# balanceladder_2026-06-09.net
KiCad netlist of a schematic drawn in EasyEDA Pro
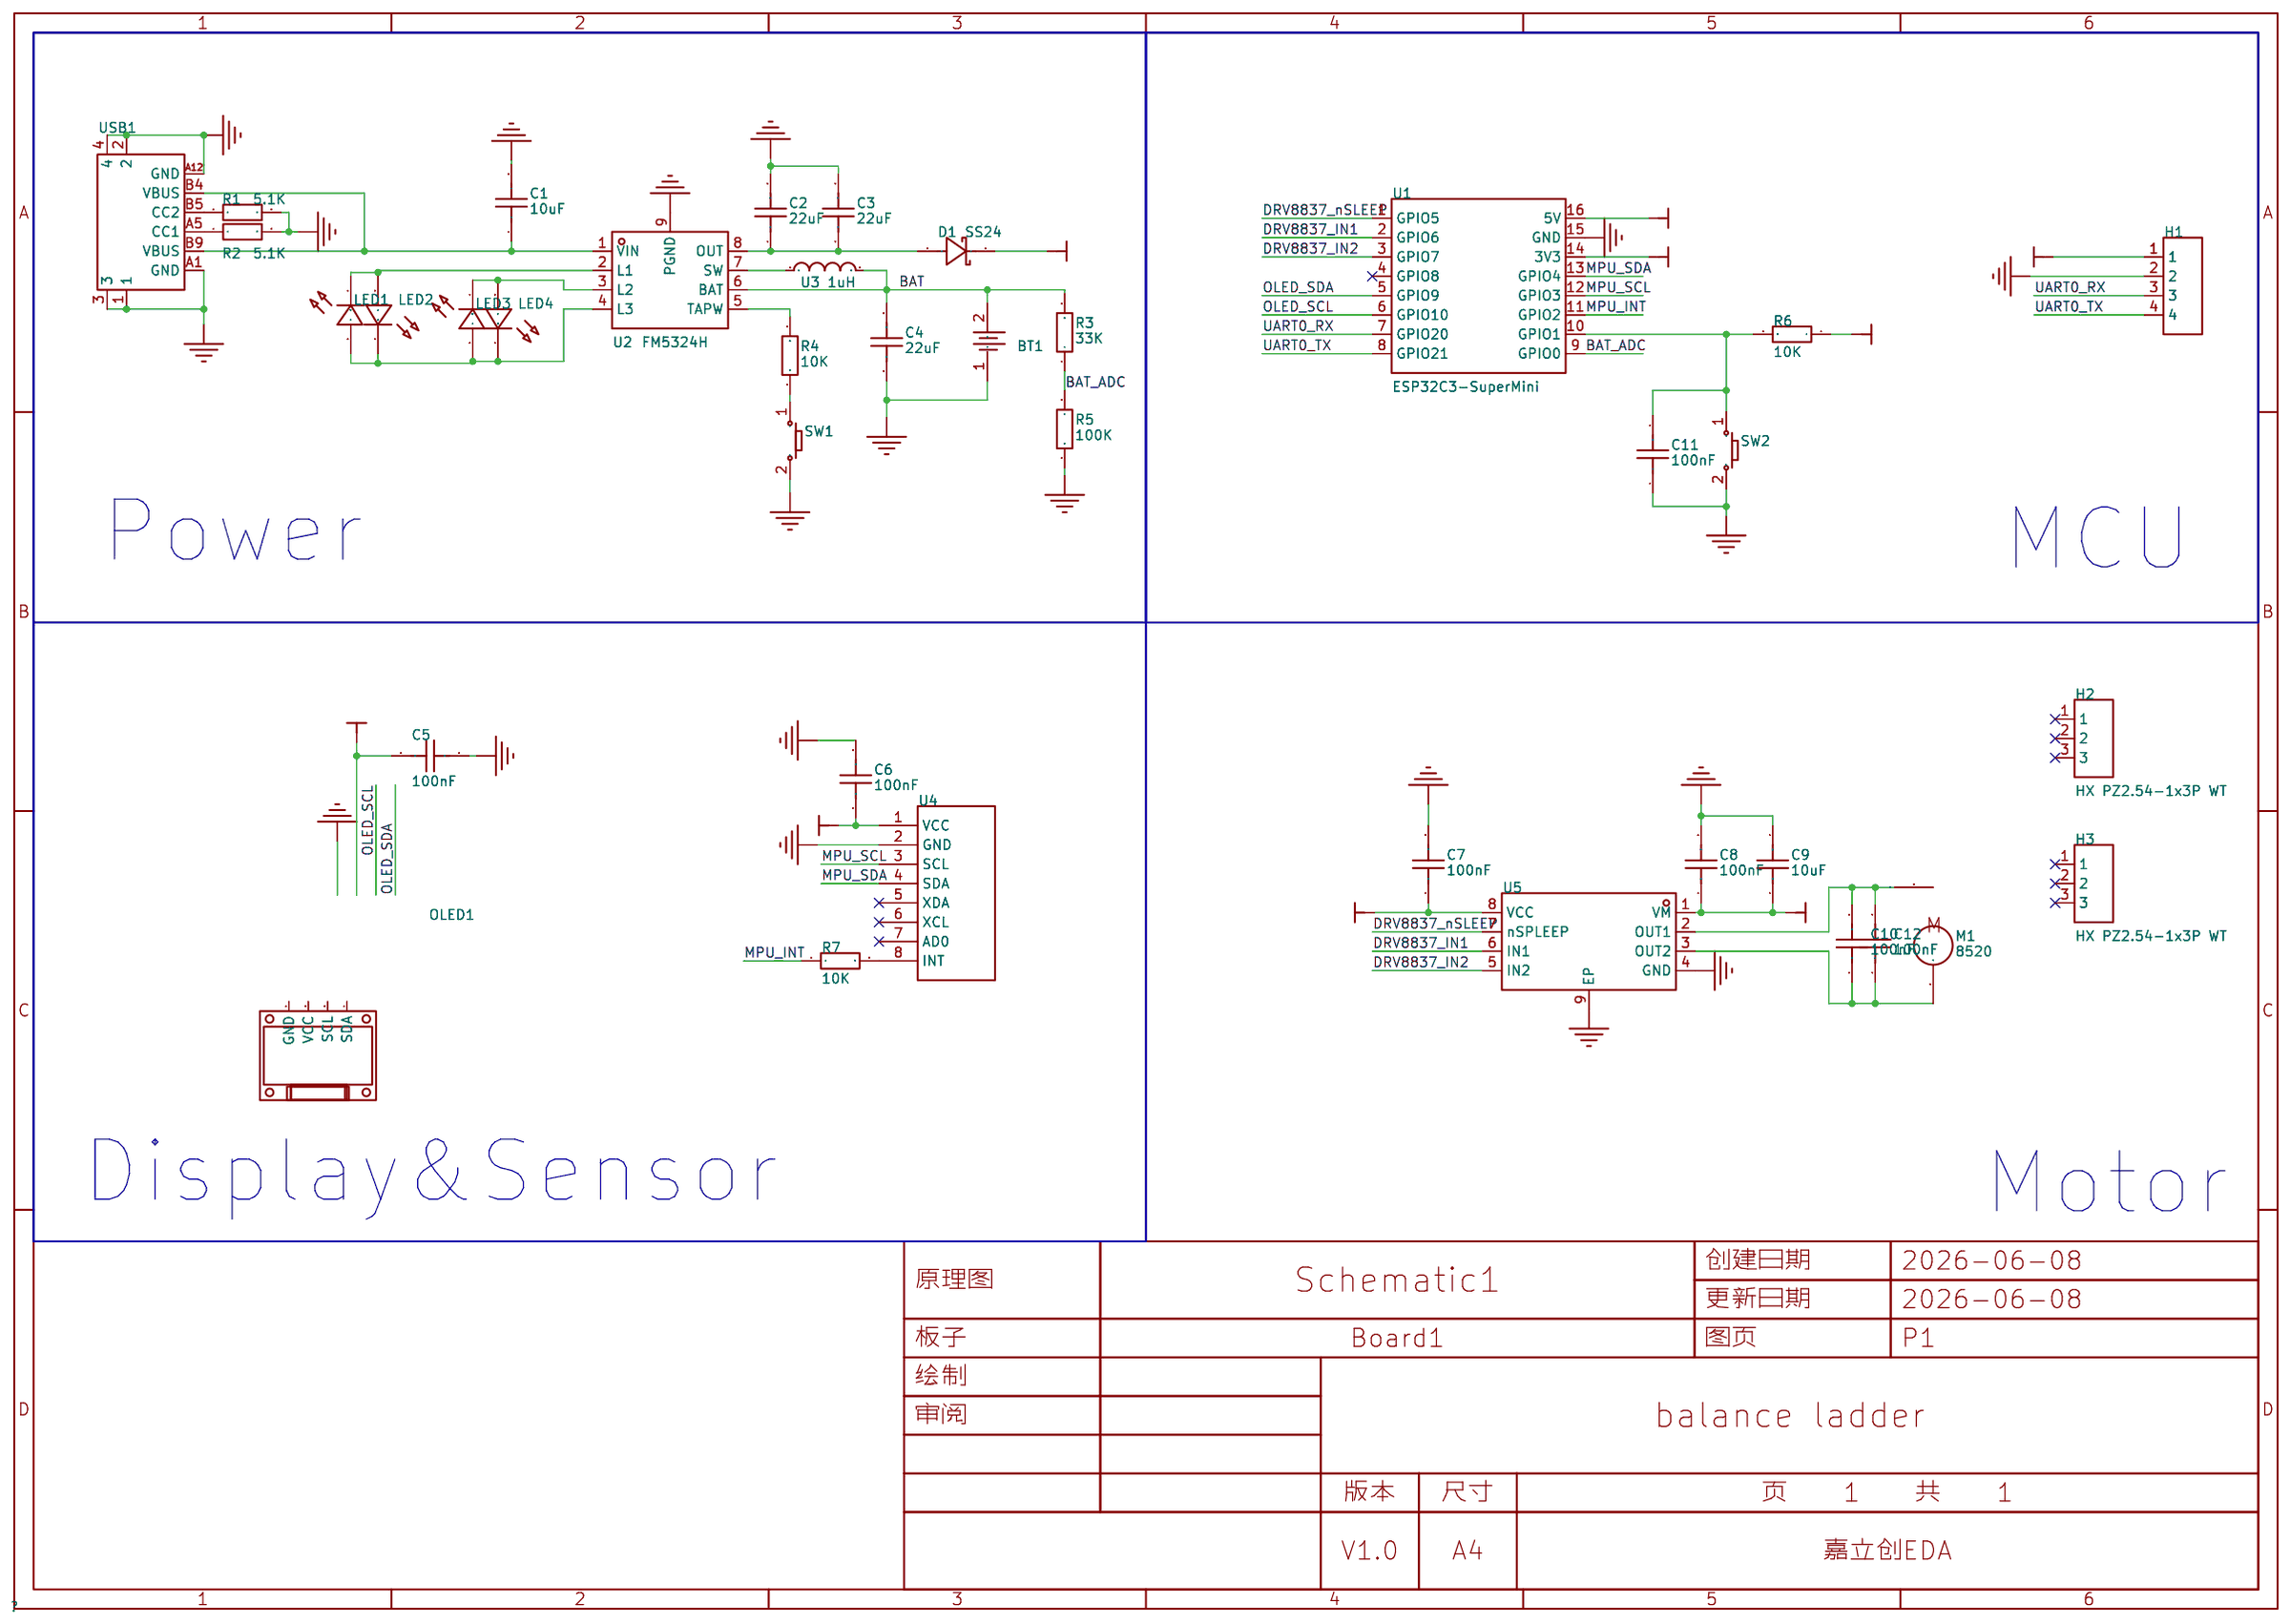
[diagram p0: schematic sheet]

(export (version "E")
  (design (tool "Eeschema 10.0.6"))
  (components
    (comp (ref "BT1")
      (value "BH-18650-B1BA002")
      (footprint "easyedapro:BATTERY-SMD_18650-1S-L77.1-W20.7-1")
      (fields (field (name "Manufacturer") "MYOUNG(美阳)"))
      (libsource (lib "easyedapro") (part "BH-18650-B1BA002"))
    )
    (comp (ref "C1")
      (value "10uF")
      (footprint "easyedapro:C0603")
      (libsource (lib "easyedapro") (part "Capacitance"))
    )
    (comp (ref "C2")
      (value "22uF")
      (footprint "easyedapro:C0603")
      (libsource (lib "easyedapro") (part "Capacitance"))
    )
    (comp (ref "C3")
      (value "22uF")
      (footprint "easyedapro:C0603")
      (libsource (lib "easyedapro") (part "Capacitance"))
    )
    (comp (ref "C4")
      (value "22uF")
      (footprint "easyedapro:C0603")
      (libsource (lib "easyedapro") (part "Capacitance"))
    )
    (comp (ref "C5")
      (value "100nF")
      (footprint "easyedapro:C0402")
      (fields
        (field (name "Manufacturer Part") "CL05B104KO5NNNC")
        (field (name "Manufacturer") "SAMSUNG(三星)")
      )
      (libsource (lib "easyedapro") (part "CL05B104KO5NNNC"))
    )
    (comp (ref "C6")
      (value "100nF")
      (footprint "easyedapro:C0402")
      (fields
        (field (name "Manufacturer Part") "CL05B104KO5NNNC")
        (field (name "Manufacturer") "SAMSUNG(三星)")
      )
      (libsource (lib "easyedapro") (part "CL05B104KO5NNNC"))
    )
    (comp (ref "C7")
      (value "100nF")
      (footprint "easyedapro:C0402")
      (fields
        (field (name "Manufacturer Part") "CL05B104KO5NNNC")
        (field (name "Manufacturer") "SAMSUNG(三星)")
      )
      (libsource (lib "easyedapro") (part "CL05B104KO5NNNC"))
    )
    (comp (ref "C8")
      (value "100nF")
      (footprint "easyedapro:C0402")
      (fields
        (field (name "Manufacturer Part") "CL05B104KO5NNNC")
        (field (name "Manufacturer") "SAMSUNG(三星)")
      )
      (libsource (lib "easyedapro") (part "CL05B104KO5NNNC"))
    )
    (comp (ref "C9")
      (value "10uF")
      (footprint "easyedapro:C0603")
      (libsource (lib "easyedapro") (part "Capacitance"))
    )
    (comp (ref "C10")
      (value "100nF")
      (footprint "easyedapro:C0402")
      (fields
        (field (name "Manufacturer Part") "CL05B104KO5NNNC")
        (field (name "Manufacturer") "SAMSUNG(三星)")
      )
      (libsource (lib "easyedapro") (part "CL05B104KO5NNNC"))
    )
    (comp (ref "C11")
      (value "100nF")
      (footprint "easyedapro:C0402")
      (description "容值:100nF;精度:±10%;额定电压:16V;温度系数:X7R;")
      (fields
        (field (name "Manufacturer Part") "CL05B104KO5NNNC")
        (field (name "Manufacturer") "SAMSUNG(三星)")
      )
      (libsource (lib "easyedapro") (part "CL05B104KO5NNNC"))
    )
    (comp (ref "C12")
      (value "100nF")
      (footprint "easyedapro:C0402")
      (description "容值:100nF;精度:±10%;额定电压:16V;温度系数:X7R;")
      (fields
        (field (name "Manufacturer Part") "CL05B104KO5NNNC")
        (field (name "Manufacturer") "SAMSUNG(三星)")
      )
      (libsource (lib "easyedapro") (part "CL05B104KO5NNNC"))
    )
    (comp (ref "D1")
      (value "SS24")
      (footprint "easyedapro:SMA_L4.3-W2.6-LS5.0-FD")
      (fields (field (name "Manufacturer") "R+O(宏嘉诚)"))
      (libsource (lib "easyedapro") (part "SS24_C7420362"))
    )
    (comp (ref "H1")
      (value "HX PZ2.54-1x4P WT")
      (footprint "easyedapro:CONN-SMD_HX-PZ2.54-1X4P-WT")
      (fields (field (name "Manufacturer") "hanxia(韩下)"))
      (libsource (lib "easyedapro") (part "HX PZ2.54-1X4P WT"))
    )
    (comp (ref "H2")
      (value "HX PZ2.54-1x3P WT")
      (footprint "easyedapro:HDR-SMD_3P-P2.54-H-M_KH-2.54PH-1X3P-L13.5-WT")
      (fields (field (name "Manufacturer") "hanxia(韩下)"))
      (libsource (lib "easyedapro") (part "HX PZ2.54-1X3P WT"))
    )
    (comp (ref "H3")
      (value "HX PZ2.54-1x3P WT")
      (footprint "easyedapro:HDR-SMD_3P-P2.54-H-M_KH-2.54PH-1X3P-L13.5-WT")
      (fields (field (name "Manufacturer") "hanxia(韩下)"))
      (libsource (lib "easyedapro") (part "HX PZ2.54-1X3P WT"))
    )
    (comp (ref "LED1")
      (value "~")
      (footprint "easyedapro:LED_0603")
      (libsource (lib "easyedapro") (part "LED_G"))
    )
    (comp (ref "LED2")
      (value "~")
      (footprint "easyedapro:LED_0603")
      (libsource (lib "easyedapro") (part "LED_G"))
    )
    (comp (ref "LED3")
      (value "~")
      (footprint "easyedapro:LED_0603")
      (libsource (lib "easyedapro") (part "LED_G"))
    )
    (comp (ref "LED4")
      (value "~")
      (footprint "easyedapro:LED_0603")
      (libsource (lib "easyedapro") (part "LED_G"))
    )
    (comp (ref "M1") (value "8520") (libsource (lib "easyedapro") (part "Motor")))
    (comp (ref "OLED1")
      (value "~")
      (footprint "easyedapro:0.96OLED_4P")
      (libsource (lib "easyedapro") (part "0.96OLED模块_4P"))
    )
    (comp (ref "R1") (value "5.1K") (footprint "easyedapro:R0603") (libsource (lib "easyedapro") (part "电阻")))
    (comp (ref "R2") (value "5.1K") (footprint "easyedapro:R0603") (libsource (lib "easyedapro") (part "电阻")))
    (comp (ref "R3") (value "33K") (footprint "easyedapro:R0603") (libsource (lib "easyedapro") (part "电阻")))
    (comp (ref "R4") (value "10K") (footprint "easyedapro:R0603") (libsource (lib "easyedapro") (part "电阻")))
    (comp (ref "R5") (value "100K") (footprint "easyedapro:R0603") (libsource (lib "easyedapro") (part "电阻")))
    (comp (ref "R6") (value "10K") (footprint "easyedapro:R0603") (libsource (lib "easyedapro") (part "电阻")))
    (comp (ref "R7") (value "10K") (footprint "easyedapro:R0402") (libsource (lib "easyedapro") (part "电阻")))
    (comp (ref "SW1")
      (value "~")
      (footprint "easyedapro:Key_SMD_3x4x2")
      (libsource (lib "easyedapro") (part "轻触按键x2"))
    )
    (comp (ref "SW2")
      (value "~")
      (footprint "easyedapro:Key_SMD_3x4x2")
      (libsource (lib "easyedapro") (part "轻触按键x2"))
    )
    (comp (ref "U1")
      (value "ESP32C3-SuperMini")
      (footprint "easyedapro:COMM-SMD_16P-L22.5-W18.0-P2.54-TL")
      (libsource (lib "easyedapro") (part "ESP32C3-SUPERMINI"))
    )
    (comp (ref "U2")
      (value "FM5324H")
      (footprint "easyedapro:ESOP-8_L4.9-W3.9-P1.27-LS6.0-BL-EP3.1")
      (fields (field (name "Manufacturer") "FM(富满)"))
      (libsource (lib "easyedapro") (part "FM5324H"))
    )
    (comp (ref "U3")
      (value "1uH")
      (footprint "easyedapro:IND-SMD_L2.5-W2.0-VLS252012CX-150M")
      (description "电感值:1uH;精度:±20%;额定电流:4A;饱和电流(Isat):5.6A;类型:-;")
      (fields
        (field (name "Manufacturer Part") "FTC252012S1R0MBCA")
        (field (name "Manufacturer") "cjiang(长江微电)")
      )
      (libsource (lib "easyedapro") (part "FTC252012S1R0MBCA"))
    )
    (comp (ref "U4") (value "~") (footprint "easyedapro:GY521") (libsource (lib "easyedapro") (part "GY521")))
    (comp (ref "U5")
      (value "DRV8837DSGR")
      (footprint "easyedapro:WSON-8_L2.0-W2.0-P0.50-TL-EP")
      (fields (field (name "Manufacturer") "TI(德州仪器)"))
      (libsource (lib "easyedapro") (part "DRV8837DSGR"))
    )
    (comp (ref "USB1")
      (value "HYCW574-USBC06-650B")
      (footprint "easyedapro:USB-C-SMD_HYCW574-USBC06-650B")
      (fields (field (name "Manufacturer") "HOAUC(华宇创)"))
      (libsource (lib "easyedapro") (part "HYCW574-USBC06-650B"))
    )
  )
  (nets
    (net (code "1") (name "+5V") (class "Default")
      (node (ref "C8") (pin "1") (pinfunction "1_1") (pintype "unspecified"))
      (node (ref "C9") (pin "1") (pinfunction "1_1") (pintype "input"))
      (node (ref "D1") (pin "2") (pinfunction "K_2") (pintype "unspecified"))
      (node (ref "U1") (pin "16") (pinfunction "5V_16") (pintype "unspecified"))
      (node (ref "U5") (pin "1") (pinfunction "VM_1") (pintype "unspecified"))
    )
    (net (code "2") (name "/BAT") (class "Default")
      (node (ref "BT1") (pin "2") (pinfunction "2_2") (pintype "input"))
      (node (ref "C4") (pin "2") (pinfunction "2_2") (pintype "input"))
      (node (ref "R3") (pin "2") (pinfunction "2_2") (pintype "input"))
      (node (ref "U2") (pin "6") (pinfunction "BAT_6") (pintype "unspecified"))
      (node (ref "U3") (pin "2") (pinfunction "2_2") (pintype "unspecified"))
    )
    (net (code "3") (name "/BAT_ADC") (class "Default")
      (node (ref "R3") (pin "1") (pinfunction "1_1") (pintype "input"))
      (node (ref "R5") (pin "2") (pinfunction "2_2") (pintype "input"))
      (node (ref "U1") (pin "9") (pinfunction "GPIO0_9") (pintype "unspecified"))
    )
    (net (code "4") (name "/DRV8837_IN1") (class "Default")
      (node (ref "U1") (pin "2") (pinfunction "GPIO6_2") (pintype "unspecified"))
      (node (ref "U5") (pin "6") (pinfunction "IN1_6") (pintype "unspecified"))
    )
    (net (code "5") (name "/DRV8837_IN2") (class "Default")
      (node (ref "U1") (pin "3") (pinfunction "GPIO7_3") (pintype "unspecified"))
      (node (ref "U5") (pin "5") (pinfunction "IN2_5") (pintype "unspecified"))
    )
    (net (code "6") (name "/DRV8837_nSLEEP") (class "Default")
      (node (ref "U1") (pin "1") (pinfunction "GPIO5_1") (pintype "unspecified"))
      (node (ref "U5") (pin "7") (pinfunction "nSPLEEP_7") (pintype "unspecified"))
    )
    (net (code "7") (name "/MPU_INT") (class "Default")
      (node (ref "R7") (pin "1") (pinfunction "1_1") (pintype "input"))
      (node (ref "U1") (pin "11") (pinfunction "GPIO2_11") (pintype "unspecified"))
    )
    (net (code "8") (name "/MPU_SCL") (class "Default")
      (node (ref "U1") (pin "12") (pinfunction "GPIO3_12") (pintype "unspecified"))
      (node (ref "U4") (pin "3") (pinfunction "SCL_3") (pintype "input"))
    )
    (net (code "9") (name "/MPU_SDA") (class "Default")
      (node (ref "U1") (pin "13") (pinfunction "GPIO4_13") (pintype "unspecified"))
      (node (ref "U4") (pin "4") (pinfunction "SDA_4") (pintype "input"))
    )
    (net (code "10") (name "/OLED_SCL") (class "Default")
      (node (ref "U1") (pin "6") (pinfunction "GPIO10_6") (pintype "unspecified"))
    )
    (net (code "11") (name "/OLED_SDA") (class "Default")
      (node (ref "U1") (pin "5") (pinfunction "GPIO9_5") (pintype "unspecified"))
    )
    (net (code "12") (name "/UART0_RX") (class "Default")
      (node (ref "H1") (pin "3") (pinfunction "3_3") (pintype "unspecified"))
      (node (ref "U1") (pin "7") (pinfunction "GPIO20_7") (pintype "unspecified"))
    )
    (net (code "13") (name "/UART0_TX") (class "Default")
      (node (ref "H1") (pin "4") (pinfunction "4_4") (pintype "unspecified"))
      (node (ref "U1") (pin "8") (pinfunction "GPIO21_8") (pintype "unspecified"))
    )
    (net (code "14") (name "GND") (class "Default")
      (node (ref "BT1") (pin "1") (pinfunction "1_1") (pintype "input"))
      (node (ref "C1") (pin "2") (pinfunction "2_2") (pintype "input"))
      (node (ref "C11") (pin "1") (pinfunction "1_1") (pintype "unspecified"))
      (node (ref "C2") (pin "2") (pinfunction "2_2") (pintype "input"))
      (node (ref "C3") (pin "2") (pinfunction "2_2") (pintype "input"))
      (node (ref "C4") (pin "1") (pinfunction "1_1") (pintype "input"))
      (node (ref "C5") (pin "1") (pinfunction "1_1") (pintype "unspecified"))
      (node (ref "C6") (pin "2") (pinfunction "2_2") (pintype "unspecified"))
      (node (ref "C7") (pin "2") (pinfunction "2_2") (pintype "unspecified"))
      (node (ref "C8") (pin "2") (pinfunction "2_2") (pintype "unspecified"))
      (node (ref "C9") (pin "2") (pinfunction "2_2") (pintype "input"))
      (node (ref "H1") (pin "2") (pinfunction "2_2") (pintype "unspecified"))
      (node (ref "R1") (pin "2") (pinfunction "2_2") (pintype "input"))
      (node (ref "R2") (pin "2") (pinfunction "2_2") (pintype "input"))
      (node (ref "R5") (pin "1") (pinfunction "1_1") (pintype "input"))
      (node (ref "SW1") (pin "2") (pinfunction "2_2") (pintype "input"))
      (node (ref "SW2") (pin "2") (pinfunction "2_2") (pintype "input"))
      (node (ref "U1") (pin "15") (pinfunction "GND_15") (pintype "unspecified"))
      (node (ref "U2") (pin "9") (pinfunction "PGND_9") (pintype "unspecified"))
      (node (ref "U4") (pin "2") (pinfunction "GND_2") (pintype "input"))
      (node (ref "U5") (pin "4") (pinfunction "GND_4") (pintype "unspecified"))
      (node (ref "U5") (pin "9") (pinfunction "EP_9") (pintype "unspecified"))
      (node (ref "USB1") (pin "1") (pinfunction "1_1") (pintype "unspecified"))
      (node (ref "USB1") (pin "2") (pinfunction "2_2") (pintype "unspecified"))
      (node (ref "USB1") (pin "3") (pinfunction "3_3") (pintype "unspecified"))
      (node (ref "USB1") (pin "4") (pinfunction "4_4") (pintype "unspecified"))
      (node (ref "USB1") (pin "A1") (pinfunction "GND_A1") (pintype "unspecified"))
      (node (ref "USB1") (pin "A12") (pinfunction "GND_A12") (pintype "unspecified"))
    )
    (net (code "15") (name "Net-(D1-A)") (class "Default")
      (node (ref "C2") (pin "1") (pinfunction "1_1") (pintype "input"))
      (node (ref "C3") (pin "1") (pinfunction "1_1") (pintype "input"))
      (node (ref "D1") (pin "1") (pinfunction "A_1") (pintype "unspecified"))
      (node (ref "U2") (pin "8") (pinfunction "OUT_8") (pintype "unspecified"))
    )
    (net (code "16") (name "Net-(LED1-A)") (class "Default")
      (node (ref "LED1") (pin "2") (pinfunction "A_2") (pintype "input"))
      (node (ref "LED2") (pin "1") (pinfunction "C_1") (pintype "input"))
      (node (ref "LED3") (pin "2") (pinfunction "A_2") (pintype "input"))
      (node (ref "LED4") (pin "1") (pinfunction "C_1") (pintype "input"))
      (node (ref "U2") (pin "4") (pinfunction "L3_4") (pintype "unspecified"))
    )
    (net (code "17") (name "Net-(LED1-C)") (class "Default")
      (node (ref "LED1") (pin "1") (pinfunction "C_1") (pintype "input"))
      (node (ref "LED2") (pin "2") (pinfunction "A_2") (pintype "input"))
      (node (ref "U2") (pin "2") (pinfunction "L1_2") (pintype "unspecified"))
    )
    (net (code "18") (name "Net-(LED3-C)") (class "Default")
      (node (ref "LED3") (pin "1") (pinfunction "C_1") (pintype "input"))
      (node (ref "LED4") (pin "2") (pinfunction "A_2") (pintype "input"))
      (node (ref "U2") (pin "3") (pinfunction "L2_3") (pintype "unspecified"))
    )
    (net (code "19") (name "Net-(R4-Pad1)") (class "Default")
      (node (ref "R4") (pin "1") (pinfunction "1_1") (pintype "input"))
      (node (ref "SW1") (pin "1") (pinfunction "1_1") (pintype "input"))
    )
    (net (code "20") (name "Net-(U1-GPIO1)") (class "Default")
      (node (ref "C11") (pin "2") (pinfunction "2_2") (pintype "unspecified"))
      (node (ref "R6") (pin "2") (pinfunction "2_2") (pintype "input"))
      (node (ref "SW2") (pin "1") (pinfunction "1_1") (pintype "input"))
      (node (ref "U1") (pin "10") (pinfunction "GPIO1_10") (pintype "unspecified"))
    )
    (net (code "21") (name "Net-(U2-SW)") (class "Default")
      (node (ref "U2") (pin "7") (pinfunction "SW_7") (pintype "unspecified"))
      (node (ref "U3") (pin "1") (pinfunction "1_1") (pintype "unspecified"))
    )
    (net (code "22") (name "Net-(U2-TAPW)") (class "Default")
      (node (ref "R4") (pin "2") (pinfunction "2_2") (pintype "input"))
      (node (ref "U2") (pin "5") (pinfunction "TAPW_5") (pintype "unspecified"))
    )
    (net (code "23") (name "Net-(U2-VIN)") (class "Default")
      (node (ref "C1") (pin "1") (pinfunction "1_1") (pintype "input"))
      (node (ref "U2") (pin "1") (pinfunction "VIN_1") (pintype "unspecified"))
      (node (ref "USB1") (pin "B4") (pinfunction "VBUS_B4") (pintype "unspecified"))
      (node (ref "USB1") (pin "B9") (pinfunction "VBUS_B9") (pintype "unspecified"))
    )
    (net (code "24") (name "Net-(U4-INT)") (class "Default")
      (node (ref "R7") (pin "2") (pinfunction "2_2") (pintype "input"))
      (node (ref "U4") (pin "8") (pinfunction "INT_8") (pintype "input"))
    )
    (net (code "25") (name "Net-(U5-OUT1)") (class "Default")
      (node (ref "C10") (pin "2") (pinfunction "2_2") (pintype "unspecified"))
      (node (ref "C12") (pin "2") (pinfunction "2_2") (pintype "unspecified"))
      (node (ref "M1") (pin "2") (pinfunction "2_2") (pintype "unspecified"))
      (node (ref "U5") (pin "2") (pinfunction "OUT1_2") (pintype "unspecified"))
    )
    (net (code "26") (name "Net-(U5-OUT2)") (class "Default")
      (node (ref "C10") (pin "1") (pinfunction "1_1") (pintype "unspecified"))
      (node (ref "C12") (pin "1") (pinfunction "1_1") (pintype "unspecified"))
      (node (ref "M1") (pin "1") (pinfunction "1_1") (pintype "unspecified"))
      (node (ref "U5") (pin "3") (pinfunction "OUT2_3") (pintype "unspecified"))
    )
    (net (code "27") (name "Net-(USB1-CC1)") (class "Default")
      (node (ref "R2") (pin "1") (pinfunction "1_1") (pintype "input"))
      (node (ref "USB1") (pin "A5") (pinfunction "CC1_A5") (pintype "unspecified"))
    )
    (net (code "28") (name "Net-(USB1-CC2)") (class "Default")
      (node (ref "R1") (pin "1") (pinfunction "1_1") (pintype "input"))
      (node (ref "USB1") (pin "B5") (pinfunction "CC2_B5") (pintype "unspecified"))
    )
    (net (code "29") (name "VCC") (class "Default")
      (node (ref "C5") (pin "2") (pinfunction "2_2") (pintype "unspecified"))
      (node (ref "C6") (pin "1") (pinfunction "1_1") (pintype "unspecified"))
      (node (ref "C7") (pin "1") (pinfunction "1_1") (pintype "unspecified"))
      (node (ref "H1") (pin "1") (pinfunction "1_1") (pintype "unspecified"))
      (node (ref "R6") (pin "1") (pinfunction "1_1") (pintype "input"))
      (node (ref "U1") (pin "14") (pinfunction "3V3_14") (pintype "unspecified"))
      (node (ref "U4") (pin "1") (pinfunction "VCC_1") (pintype "input"))
      (node (ref "U5") (pin "8") (pinfunction "VCC_8") (pintype "unspecified"))
    )
    (net (code "30") (name "unconnected-(H2-Pad1)") (class "Default")
      (node (ref "H2") (pin "1") (pinfunction "1_1") (pintype "unspecified+no_connect"))
    )
    (net (code "31") (name "unconnected-(H2-Pad2)") (class "Default")
      (node (ref "H2") (pin "2") (pinfunction "2_2") (pintype "unspecified+no_connect"))
    )
    (net (code "32") (name "unconnected-(H2-Pad3)") (class "Default")
      (node (ref "H2") (pin "3") (pinfunction "3_3") (pintype "unspecified+no_connect"))
    )
    (net (code "33") (name "unconnected-(H3-Pad1)") (class "Default")
      (node (ref "H3") (pin "1") (pinfunction "1_1") (pintype "unspecified+no_connect"))
    )
    (net (code "34") (name "unconnected-(H3-Pad2)") (class "Default")
      (node (ref "H3") (pin "2") (pinfunction "2_2") (pintype "unspecified+no_connect"))
    )
    (net (code "35") (name "unconnected-(H3-Pad3)") (class "Default")
      (node (ref "H3") (pin "3") (pinfunction "3_3") (pintype "unspecified+no_connect"))
    )
    (net (code "36") (name "unconnected-(OLED1-GND-Pad1)") (class "Default")
      (node (ref "OLED1") (pin "1") (pinfunction "GND_1") (pintype "input"))
    )
    (net (code "37") (name "unconnected-(OLED1-SCL-Pad3)") (class "Default")
      (node (ref "OLED1") (pin "3") (pinfunction "SCL_3") (pintype "input"))
    )
    (net (code "38") (name "unconnected-(OLED1-SDA-Pad4)") (class "Default")
      (node (ref "OLED1") (pin "4") (pinfunction "SDA_4") (pintype "input"))
    )
    (net (code "39") (name "unconnected-(OLED1-VCC-Pad2)") (class "Default")
      (node (ref "OLED1") (pin "2") (pinfunction "VCC_2") (pintype "input"))
    )
    (net (code "40") (name "unconnected-(U1-GPIO8-Pad4)") (class "Default")
      (node (ref "U1") (pin "4") (pinfunction "GPIO8_4") (pintype "unspecified+no_connect"))
    )
    (net (code "41") (name "unconnected-(U4-AD0-Pad7)") (class "Default")
      (node (ref "U4") (pin "7") (pinfunction "AD0_7") (pintype "input+no_connect"))
    )
    (net (code "42") (name "unconnected-(U4-XCL-Pad6)") (class "Default")
      (node (ref "U4") (pin "6") (pinfunction "XCL_6") (pintype "input+no_connect"))
    )
    (net (code "43") (name "unconnected-(U4-XDA-Pad5)") (class "Default")
      (node (ref "U4") (pin "5") (pinfunction "XDA_5") (pintype "input+no_connect"))
    )
  )
)
